# Support.net
KiCad netlist of a schematic drawn in Altium Designer
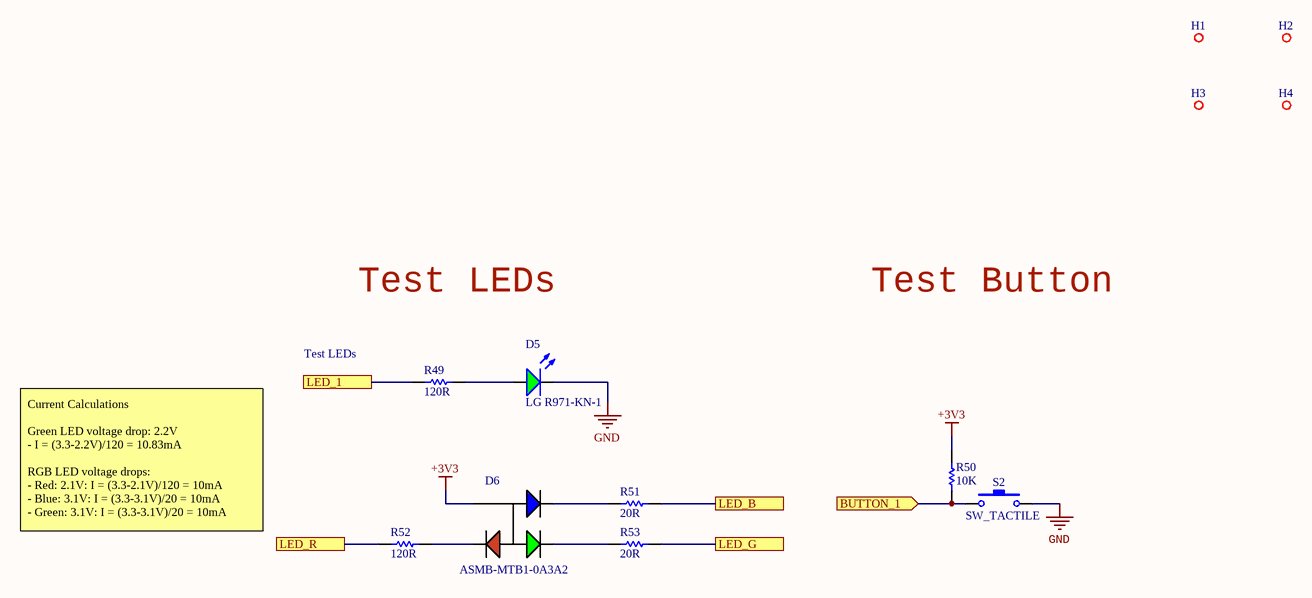
[diagram p0: Support.SchDoc]

(export (version "E")
  (design (tool "Eeschema 10.0.6"))
  (components
    (comp (ref "D5")
      (value "LG R971-KN-1")
      (footprint "LED_0805_LINE")
      (description "LED GREEN DIFFUSED 0805 SMD")
      (libsource (lib "UWRT_Schematic_Library_2020") (part "DIO_LED_G"))
    )
    (comp (ref "D6")
      (value "LED_RGB")
      (footprint "LED_RGB")
      (description "LED RGB DIFFUSED 4PLCC SMD")
      (fields (field (name "MANUFACTURER PART NUMBER 1") "ASMB-MTB1-0A3A2"))
      (libsource (lib "UWRT_Schematic_Library_2020") (part "LED_RGB"))
    )
    (comp (ref "H1")
      (value "MOUNTING_HOLES")
      (footprint "MOUNTING_HOLE")
      (description "6cm x 6cm")
      (libsource (lib "UWRT_Schematic_Library_2020") (part "MOUNTING_HOLES"))
    )
    (comp (ref "H2")
      (value "MOUNTING_HOLES")
      (footprint "MOUNTING_HOLE")
      (description "6cm x 6cm")
      (libsource (lib "UWRT_Schematic_Library_2020") (part "MOUNTING_HOLES"))
    )
    (comp (ref "H3")
      (value "MOUNTING_HOLES")
      (footprint "MOUNTING_HOLE")
      (description "6cm x 6cm")
      (libsource (lib "UWRT_Schematic_Library_2020") (part "MOUNTING_HOLES"))
    )
    (comp (ref "H4")
      (value "MOUNTING_HOLES")
      (footprint "MOUNTING_HOLE")
      (description "6cm x 6cm")
      (libsource (lib "UWRT_Schematic_Library_2020") (part "MOUNTING_HOLES"))
    )
    (comp (ref "R49")
      (value "120R")
      (footprint "RESC0603(1608)_N")
      (description "RES SMD 120 OHM 5% 1/10W 0603")
      (fields (field (name "MANUFACTURER") "Yageo") (field (name "MPN") "RC0603JR-07120RL"))
      (libsource (lib "UWRT_Schematic_Library_2020") (part "RES_120R_0603"))
    )
    (comp (ref "R50")
      (value "10K")
      (footprint "RESC0603(1608)_N")
      (description "RES SMD 10K OHM 5% 1/10W 0603")
      (fields (field (name "MANUFACTURER") "Yageo") (field (name "MPN") "RC0603JR-0710KL"))
      (libsource (lib "UWRT_Schematic_Library_2020") (part "RES_10K_0603"))
    )
    (comp (ref "R51")
      (value "20R")
      (footprint "RESC0603(1608)_N")
      (description "RES SMD 20 OHM 5% 1/10W 0603")
      (fields (field (name "MANUFACTURER") "Yageo") (field (name "MPN") "RC0603JR-0720RL"))
      (libsource (lib "UWRT_Schematic_Library_2020") (part "RES_20R_0603"))
    )
    (comp (ref "R52")
      (value "120R")
      (footprint "RESC0603(1608)_N")
      (description "RES SMD 120 OHM 5% 1/10W 0603")
      (fields (field (name "MANUFACTURER") "Yageo") (field (name "MPN") "RC0603JR-07120RL"))
      (libsource (lib "UWRT_Schematic_Library_2020") (part "RES_120R_0603"))
    )
    (comp (ref "R53")
      (value "20R")
      (footprint "RESC0603(1608)_N")
      (description "RES SMD 20 OHM 5% 1/10W 0603")
      (fields (field (name "MANUFACTURER") "Yageo") (field (name "MPN") "RC0603JR-0720RL"))
      (libsource (lib "UWRT_Schematic_Library_2020") (part "RES_20R_0603"))
    )
    (comp (ref "S2")
      (value "SW_TACTILE")
      (footprint "B3U-1000P")
      (description "Tactile Switch (Grey)")
      (libsource (lib "UWRT_Schematic_Library_2020") (part "SW_TACTILE"))
    )
  )
  (nets
    (net (code "1") (name "+3V3") (class "Default")
      (node (ref "D6") (pin "4") (pinfunction "9_4") (pintype "passive"))
      (node (ref "R50") (pin "2") (pinfunction "2_2") (pintype "passive"))
    )
    (net (code "2") (name "/BUTTON_1") (class "Default")
      (node (ref "R50") (pin "1") (pinfunction "1_1") (pintype "passive"))
      (node (ref "S2") (pin "1") (pinfunction "1_1") (pintype "passive"))
    )
    (net (code "3") (name "/LED_1") (class "Default")
      (node (ref "R49") (pin "1") (pinfunction "1_1") (pintype "passive"))
    )
    (net (code "4") (name "/LED_B") (class "Default")
      (node (ref "R51") (pin "2") (pinfunction "2_2") (pintype "passive"))
    )
    (net (code "5") (name "/LED_G") (class "Default")
      (node (ref "R53") (pin "2") (pinfunction "2_2") (pintype "passive"))
    )
    (net (code "6") (name "/LED_R") (class "Default")
      (node (ref "R52") (pin "1") (pinfunction "1_1") (pintype "passive"))
    )
    (net (code "7") (name "GND") (class "Default")
      (node (ref "D5") (pin "2") (pinfunction "K_2") (pintype "passive"))
      (node (ref "S2") (pin "2") (pinfunction "2_2") (pintype "passive"))
    )
    (net (code "8") (name "Net-(D5-A)") (class "Default")
      (node (ref "D5") (pin "1") (pinfunction "A_1") (pintype "passive"))
      (node (ref "R49") (pin "2") (pinfunction "2_2") (pintype "passive"))
    )
    (net (code "9") (name "Net-(D6-10)") (class "Default")
      (node (ref "D6") (pin "3") (pinfunction "10_3") (pintype "passive"))
      (node (ref "R51") (pin "1") (pinfunction "1_1") (pintype "passive"))
    )
    (net (code "10") (name "Net-(D6-11)") (class "Default")
      (node (ref "D6") (pin "1") (pinfunction "11_1") (pintype "passive"))
      (node (ref "R52") (pin "2") (pinfunction "2_2") (pintype "passive"))
    )
    (net (code "11") (name "Net-(D6-12)") (class "Default")
      (node (ref "D6") (pin "2") (pinfunction "12_2") (pintype "passive"))
      (node (ref "R53") (pin "1") (pinfunction "1_1") (pintype "passive"))
    )
  )
)
